# 513_lora_raspberrypi.net
KiCad netlist of a schematic drawn in EAGLE
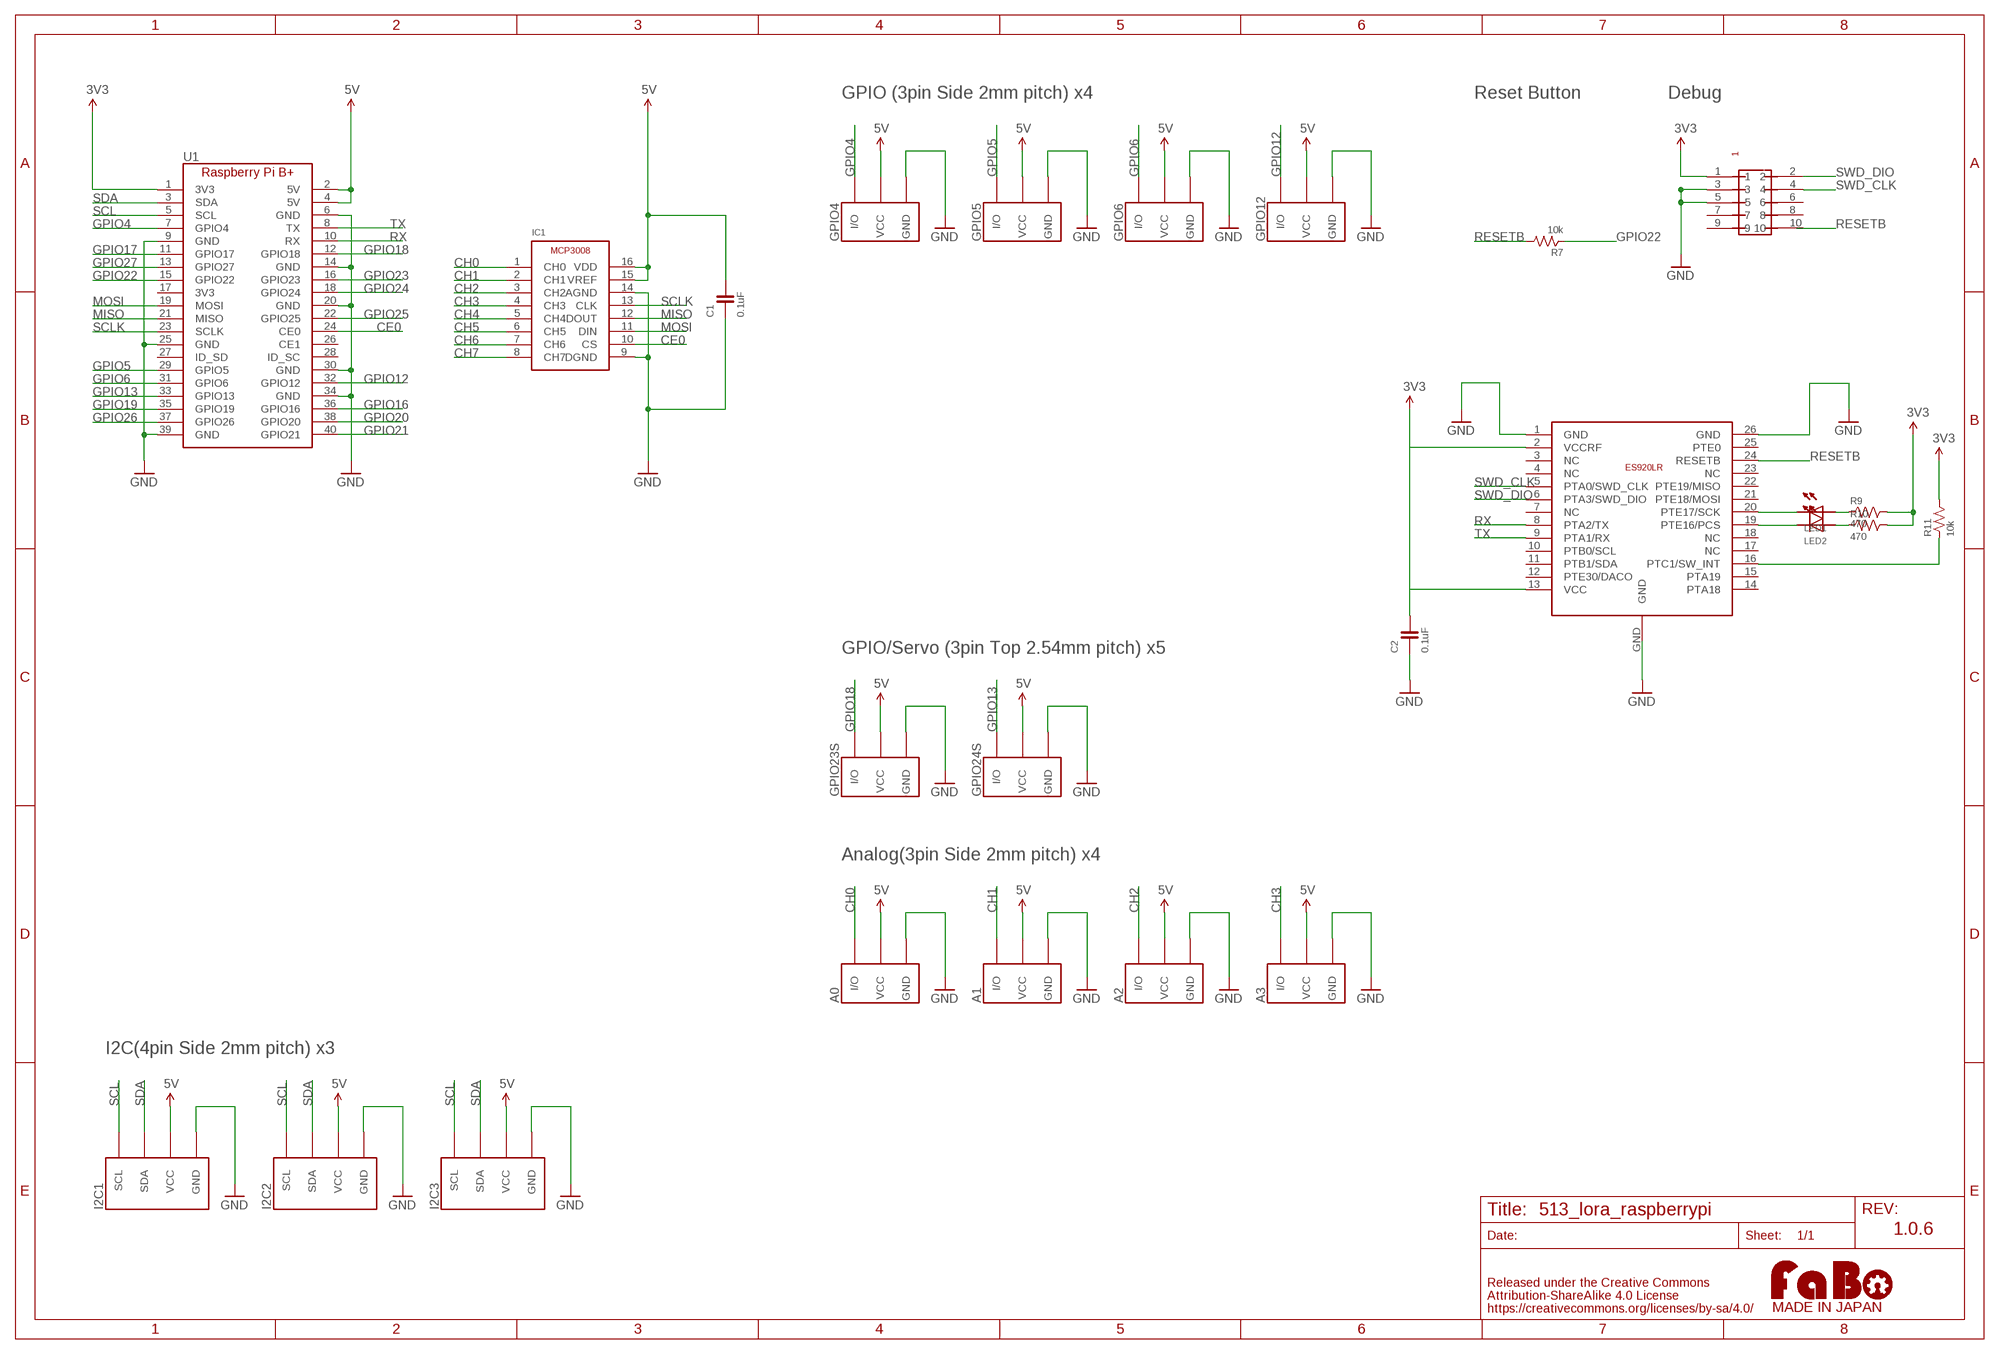
[diagram p0: schematic, sheet 1]

(export (version "E")
  (design (tool "Eeschema 10.0.6"))
  (components
    (comp (ref "A0")
      (value "FABO_BRICK_3PIN-B03B-PASK-1")
      (footprint "eagle-import:FABO_BRICK_3PIN_B03B-PASK-1")
      (libsource (lib "eagle-import") (part "FABO_BRICK_3PIN-B03B-PASK-1"))
    )
    (comp (ref "A1")
      (value "FABO_BRICK_3PIN-B03B-PASK-1")
      (footprint "eagle-import:FABO_BRICK_3PIN_B03B-PASK-1")
      (libsource (lib "eagle-import") (part "FABO_BRICK_3PIN-B03B-PASK-1"))
    )
    (comp (ref "A2")
      (value "FABO_BRICK_3PIN-B03B-PASK-1")
      (footprint "eagle-import:FABO_BRICK_3PIN_B03B-PASK-1")
      (libsource (lib "eagle-import") (part "FABO_BRICK_3PIN-B03B-PASK-1"))
    )
    (comp (ref "A3")
      (value "FABO_BRICK_3PIN-B03B-PASK-1")
      (footprint "eagle-import:FABO_BRICK_3PIN_B03B-PASK-1")
      (libsource (lib "eagle-import") (part "FABO_BRICK_3PIN-B03B-PASK-1"))
    )
    (comp (ref "C1")
      (value "0.1uF")
      (footprint "eagle-import:0603")
      (libsource (lib "eagle-import") (part "CAPACITOR-0603"))
    )
    (comp (ref "C2")
      (value "0.1uF")
      (footprint "eagle-import:0603-NARROW")
      (libsource (lib "eagle-import") (part "CAPACITOR-0603_NARROW"))
    )
    (comp (ref "GPIO4")
      (value "FABO_BRICK_3PIN-S03B-PASK-2")
      (footprint "eagle-import:FABO_BRICK_3PIN_S03B-PASK-2")
      (libsource (lib "eagle-import") (part "FABO_BRICK_3PIN-S03B-PASK-2"))
    )
    (comp (ref "GPIO5")
      (value "FABO_BRICK_3PIN-S03B-PASK-2")
      (footprint "eagle-import:FABO_BRICK_3PIN_S03B-PASK-2")
      (libsource (lib "eagle-import") (part "FABO_BRICK_3PIN-S03B-PASK-2"))
    )
    (comp (ref "GPIO6")
      (value "FABO_BRICK_3PIN-S03B-PASK-2")
      (footprint "eagle-import:FABO_BRICK_3PIN_S03B-PASK-2")
      (libsource (lib "eagle-import") (part "FABO_BRICK_3PIN-S03B-PASK-2"))
    )
    (comp (ref "GPIO12")
      (value "FABO_BRICK_3PIN-S03B-PASK-2")
      (footprint "eagle-import:FABO_BRICK_3PIN_S03B-PASK-2")
      (libsource (lib "eagle-import") (part "FABO_BRICK_3PIN-S03B-PASK-2"))
    )
    (comp (ref "GPIO23S")
      (value "FABO_BRICK_3PIN-HEADER")
      (footprint "eagle-import:FABO_BRICK_3PIN_HEADER")
      (libsource (lib "eagle-import") (part "FABO_BRICK_3PIN-HEADER"))
    )
    (comp (ref "GPIO24S")
      (value "FABO_BRICK_3PIN-HEADER")
      (footprint "eagle-import:FABO_BRICK_3PIN_HEADER")
      (libsource (lib "eagle-import") (part "FABO_BRICK_3PIN-HEADER"))
    )
    (comp (ref "I2C1")
      (value "FABO_BRICK_I2C-S04B-PASK-2")
      (footprint "eagle-import:FABO_BRICK_I2C_S04B-PASK-2")
      (libsource (lib "eagle-import") (part "FABO_BRICK_I2C-S04B-PASK-2"))
    )
    (comp (ref "I2C2")
      (value "FABO_BRICK_I2C-S04B-PASK-2")
      (footprint "eagle-import:FABO_BRICK_I2C_S04B-PASK-2")
      (libsource (lib "eagle-import") (part "FABO_BRICK_I2C-S04B-PASK-2"))
    )
    (comp (ref "I2C3")
      (value "FABO_BRICK_I2C-S04B-PASK-2")
      (footprint "eagle-import:FABO_BRICK_I2C_S04B-PASK-2")
      (libsource (lib "eagle-import") (part "FABO_BRICK_I2C-S04B-PASK-2"))
    )
    (comp (ref "IC1")
      (value "MICROCHIP-MCP3008")
      (footprint "eagle-import:MICROCHIP-MCP3008")
      (libsource (lib "eagle-import") (part "MICROCHIP-MCP3008"))
    )
    (comp (ref "LED1")
      (value "LED-0603")
      (footprint "eagle-import:0603")
      (libsource (lib "eagle-import") (part "LED-0603"))
    )
    (comp (ref "LED2")
      (value "LED-0603")
      (footprint "eagle-import:0603")
      (libsource (lib "eagle-import") (part "LED-0603"))
    )
    (comp (ref "R7")
      (value "10k")
      (footprint "eagle-import:0603-NARROW")
      (libsource (lib "eagle-import") (part "RESISTOR-0603-NARROW"))
    )
    (comp (ref "R9")
      (value "470")
      (footprint "eagle-import:0603-NARROW")
      (libsource (lib "eagle-import") (part "RESISTOR-0603-NARROW"))
    )
    (comp (ref "R10")
      (value "470")
      (footprint "eagle-import:0603-NARROW")
      (libsource (lib "eagle-import") (part "RESISTOR-0603-NARROW"))
    )
    (comp (ref "R11")
      (value "10k")
      (footprint "eagle-import:0603-NARROW")
      (libsource (lib "eagle-import") (part "RESISTOR-0603-NARROW"))
    )
    (comp (ref "U$14")
      (value "LOGO_FABO-M")
      (footprint "eagle-import:LOGO_FABO_MS")
      (libsource (lib "eagle-import") (part "LOGO_FABO-M"))
    )
    (comp (ref "U$15")
      (value "PIN-HEADER-SMT(1.27MM)2X5")
      (footprint "eagle-import:PIN-HEADER-SMT(1.27MM)2X5")
      (libsource (lib "eagle-import") (part "PIN-HEADER-SMT(1.27MM)2X5"))
    )
    (comp (ref "U$16")
      (value "ES920LR")
      (footprint "eagle-import:ES920LR")
      (libsource (lib "eagle-import") (part "ES920LR"))
    )
    (comp (ref "U1")
      (value "RASPBERRY_PI_B+")
      (footprint "eagle-import:RASPBERRY_PI_B+")
      (libsource (lib "eagle-import") (part "RASPBERRY_PI_B+"))
    )
  )
  (nets
    (net (code "1") (name "/CE0") (class "Default")
      (node (ref "IC1") (pin "10") (pinfunction "CS_10") (pintype "bidirectional"))
      (node (ref "U1") (pin "24") (pinfunction "CE0_24") (pintype "bidirectional"))
    )
    (net (code "2") (name "/CH0") (class "Default")
      (node (ref "A0") (pin "I/O") (pinfunction "I/O_I/O") (pintype "bidirectional"))
      (node (ref "IC1") (pin "1") (pinfunction "CH0_1") (pintype "bidirectional"))
    )
    (net (code "3") (name "/CH1") (class "Default")
      (node (ref "A1") (pin "I/O") (pinfunction "I/O_I/O") (pintype "bidirectional"))
      (node (ref "IC1") (pin "2") (pinfunction "CH1_2") (pintype "bidirectional"))
    )
    (net (code "4") (name "/CH2") (class "Default")
      (node (ref "A2") (pin "I/O") (pinfunction "I/O_I/O") (pintype "bidirectional"))
      (node (ref "IC1") (pin "3") (pinfunction "CH2_3") (pintype "bidirectional"))
    )
    (net (code "5") (name "/CH3") (class "Default")
      (node (ref "A3") (pin "I/O") (pinfunction "I/O_I/O") (pintype "bidirectional"))
      (node (ref "IC1") (pin "4") (pinfunction "CH3_4") (pintype "bidirectional"))
    )
    (net (code "6") (name "/CH4") (class "Default")
      (node (ref "IC1") (pin "5") (pinfunction "CH4_5") (pintype "bidirectional"))
    )
    (net (code "7") (name "/CH5") (class "Default")
      (node (ref "IC1") (pin "6") (pinfunction "CH5_6") (pintype "bidirectional"))
    )
    (net (code "8") (name "/CH6") (class "Default")
      (node (ref "IC1") (pin "7") (pinfunction "CH6_7") (pintype "bidirectional"))
    )
    (net (code "9") (name "/CH7") (class "Default")
      (node (ref "IC1") (pin "8") (pinfunction "CH7_8") (pintype "bidirectional"))
    )
    (net (code "10") (name "/GPIO4") (class "Default")
      (node (ref "GPIO4") (pin "I/O") (pinfunction "I/O_I/O") (pintype "bidirectional"))
      (node (ref "U1") (pin "7") (pinfunction "GPIO4_7") (pintype "bidirectional"))
    )
    (net (code "11") (name "/GPIO5") (class "Default")
      (node (ref "GPIO5") (pin "I/O") (pinfunction "I/O_I/O") (pintype "bidirectional"))
      (node (ref "U1") (pin "29") (pinfunction "GPIO5_29") (pintype "bidirectional"))
    )
    (net (code "12") (name "/GPIO6") (class "Default")
      (node (ref "GPIO6") (pin "I/O") (pinfunction "I/O_I/O") (pintype "bidirectional"))
      (node (ref "U1") (pin "31") (pinfunction "GPIO6_31") (pintype "bidirectional"))
    )
    (net (code "13") (name "/GPIO12") (class "Default")
      (node (ref "GPIO12") (pin "I/O") (pinfunction "I/O_I/O") (pintype "bidirectional"))
      (node (ref "U1") (pin "32") (pinfunction "GPIO12_32") (pintype "bidirectional"))
    )
    (net (code "14") (name "/GPIO13") (class "Default")
      (node (ref "GPIO24S") (pin "I/O") (pinfunction "I/O_I/O") (pintype "bidirectional"))
      (node (ref "U1") (pin "33") (pinfunction "GPIO13_33") (pintype "bidirectional"))
    )
    (net (code "15") (name "/GPIO16") (class "Default")
      (node (ref "U1") (pin "36") (pinfunction "GPIO16_36") (pintype "bidirectional"))
    )
    (net (code "16") (name "/GPIO17") (class "Default")
      (node (ref "U1") (pin "11") (pinfunction "GPIO17_11") (pintype "bidirectional"))
    )
    (net (code "17") (name "/GPIO18") (class "Default")
      (node (ref "GPIO23S") (pin "I/O") (pinfunction "I/O_I/O") (pintype "bidirectional"))
      (node (ref "U1") (pin "12") (pinfunction "GPIO18_12") (pintype "bidirectional"))
    )
    (net (code "18") (name "/GPIO19") (class "Default")
      (node (ref "U1") (pin "35") (pinfunction "GPIO19_35") (pintype "bidirectional"))
    )
    (net (code "19") (name "/GPIO20") (class "Default")
      (node (ref "U1") (pin "38") (pinfunction "GPIO20_38") (pintype "bidirectional"))
    )
    (net (code "20") (name "/GPIO21") (class "Default")
      (node (ref "U1") (pin "40") (pinfunction "GPIO21_40") (pintype "bidirectional"))
    )
    (net (code "21") (name "/GPIO22") (class "Default")
      (node (ref "R7") (pin "1") (pinfunction "1_1") (pintype "bidirectional"))
      (node (ref "U1") (pin "15") (pinfunction "GPIO22_15") (pintype "bidirectional"))
    )
    (net (code "22") (name "/GPIO23") (class "Default")
      (node (ref "U1") (pin "16") (pinfunction "GPIO23_16") (pintype "bidirectional"))
    )
    (net (code "23") (name "/GPIO24") (class "Default")
      (node (ref "U1") (pin "18") (pinfunction "GPIO24_18") (pintype "bidirectional"))
    )
    (net (code "24") (name "/GPIO25") (class "Default")
      (node (ref "U1") (pin "22") (pinfunction "GPIO25_22") (pintype "bidirectional"))
    )
    (net (code "25") (name "/GPIO26") (class "Default")
      (node (ref "U1") (pin "37") (pinfunction "GPIO26_37") (pintype "bidirectional"))
    )
    (net (code "26") (name "/GPIO27") (class "Default")
      (node (ref "U1") (pin "13") (pinfunction "GPIO27_13") (pintype "bidirectional"))
    )
    (net (code "27") (name "/MISO") (class "Default")
      (node (ref "IC1") (pin "12") (pinfunction "DOUT_12") (pintype "bidirectional"))
      (node (ref "U1") (pin "21") (pinfunction "MISO_21") (pintype "bidirectional"))
    )
    (net (code "28") (name "/MOSI") (class "Default")
      (node (ref "IC1") (pin "11") (pinfunction "DIN_11") (pintype "bidirectional"))
      (node (ref "U1") (pin "19") (pinfunction "MOSI_19") (pintype "bidirectional"))
    )
    (net (code "29") (name "/RESETB") (class "Default")
      (node (ref "R7") (pin "2") (pinfunction "2_2") (pintype "bidirectional"))
      (node (ref "U$15") (pin "10") (pinfunction "10_10") (pintype "bidirectional"))
      (node (ref "U$16") (pin "24") (pinfunction "RESETB_24") (pintype "bidirectional"))
    )
    (net (code "30") (name "/RX") (class "Default")
      (node (ref "U$16") (pin "8") (pinfunction "PTA2/TX_8") (pintype "bidirectional"))
      (node (ref "U1") (pin "10") (pinfunction "RX_10") (pintype "bidirectional"))
    )
    (net (code "31") (name "/SCL") (class "Default")
      (node (ref "I2C1") (pin "SCL") (pinfunction "SCL_SCL") (pintype "bidirectional"))
      (node (ref "I2C2") (pin "SCL") (pinfunction "SCL_SCL") (pintype "bidirectional"))
      (node (ref "I2C3") (pin "SCL") (pinfunction "SCL_SCL") (pintype "bidirectional"))
      (node (ref "U1") (pin "5") (pinfunction "SCL_5") (pintype "bidirectional"))
    )
    (net (code "32") (name "/SCLK") (class "Default")
      (node (ref "IC1") (pin "13") (pinfunction "CLK_13") (pintype "bidirectional"))
      (node (ref "U1") (pin "23") (pinfunction "SCLK_23") (pintype "bidirectional"))
    )
    (net (code "33") (name "/SDA") (class "Default")
      (node (ref "I2C1") (pin "SDA") (pinfunction "SDA_SDA") (pintype "bidirectional"))
      (node (ref "I2C2") (pin "SDA") (pinfunction "SDA_SDA") (pintype "bidirectional"))
      (node (ref "I2C3") (pin "SDA") (pinfunction "SDA_SDA") (pintype "bidirectional"))
      (node (ref "U1") (pin "3") (pinfunction "SDA_3") (pintype "bidirectional"))
    )
    (net (code "34") (name "/SWD_CLK") (class "Default")
      (node (ref "U$15") (pin "4") (pinfunction "4_4") (pintype "bidirectional"))
      (node (ref "U$16") (pin "5") (pinfunction "PTA0/SWD_CLK_5") (pintype "bidirectional"))
    )
    (net (code "35") (name "/SWD_DIO") (class "Default")
      (node (ref "U$15") (pin "2") (pinfunction "2_2") (pintype "bidirectional"))
      (node (ref "U$16") (pin "6") (pinfunction "PTA3/SWD_DIO_6") (pintype "bidirectional"))
    )
    (net (code "36") (name "/TX") (class "Default")
      (node (ref "U$16") (pin "9") (pinfunction "PTA1/RX_9") (pintype "bidirectional"))
      (node (ref "U1") (pin "8") (pinfunction "TX_8") (pintype "bidirectional"))
    )
    (net (code "37") (name "3V3") (class "Default")
      (node (ref "C2") (pin "2") (pinfunction "2_2") (pintype "passive"))
      (node (ref "R10") (pin "2") (pinfunction "2_2") (pintype "bidirectional"))
      (node (ref "R11") (pin "2") (pinfunction "2_2") (pintype "bidirectional"))
      (node (ref "R9") (pin "2") (pinfunction "2_2") (pintype "bidirectional"))
      (node (ref "U$15") (pin "1") (pinfunction "1_1") (pintype "bidirectional"))
      (node (ref "U$16") (pin "13") (pinfunction "VCC_13") (pintype "bidirectional"))
      (node (ref "U$16") (pin "2") (pinfunction "VCCRF_2") (pintype "bidirectional"))
      (node (ref "U1") (pin "1") (pinfunction "3V3_1") (pintype "bidirectional"))
    )
    (net (code "38") (name "5V") (class "Default")
      (node (ref "A0") (pin "VCC") (pinfunction "VCC_VCC") (pintype "bidirectional"))
      (node (ref "A1") (pin "VCC") (pinfunction "VCC_VCC") (pintype "bidirectional"))
      (node (ref "A2") (pin "VCC") (pinfunction "VCC_VCC") (pintype "bidirectional"))
      (node (ref "A3") (pin "VCC") (pinfunction "VCC_VCC") (pintype "bidirectional"))
      (node (ref "C1") (pin "2") (pinfunction "2_2") (pintype "passive"))
      (node (ref "GPIO12") (pin "VCC") (pinfunction "VCC_VCC") (pintype "bidirectional"))
      (node (ref "GPIO23S") (pin "VCC") (pinfunction "VCC_VCC") (pintype "bidirectional"))
      (node (ref "GPIO24S") (pin "VCC") (pinfunction "VCC_VCC") (pintype "bidirectional"))
      (node (ref "GPIO4") (pin "VCC") (pinfunction "VCC_VCC") (pintype "bidirectional"))
      (node (ref "GPIO5") (pin "VCC") (pinfunction "VCC_VCC") (pintype "bidirectional"))
      (node (ref "GPIO6") (pin "VCC") (pinfunction "VCC_VCC") (pintype "bidirectional"))
      (node (ref "I2C1") (pin "VCC") (pinfunction "VCC_VCC") (pintype "bidirectional"))
      (node (ref "I2C2") (pin "VCC") (pinfunction "VCC_VCC") (pintype "bidirectional"))
      (node (ref "I2C3") (pin "VCC") (pinfunction "VCC_VCC") (pintype "bidirectional"))
      (node (ref "IC1") (pin "15") (pinfunction "VREF_15") (pintype "bidirectional"))
      (node (ref "IC1") (pin "16") (pinfunction "VDD_16") (pintype "bidirectional"))
      (node (ref "U1") (pin "2") (pinfunction "5V_2") (pintype "bidirectional"))
      (node (ref "U1") (pin "4") (pinfunction "5V_4") (pintype "bidirectional"))
    )
    (net (code "39") (name "GND") (class "Default")
      (node (ref "A0") (pin "GND") (pinfunction "GND_GND") (pintype "bidirectional"))
      (node (ref "A1") (pin "GND") (pinfunction "GND_GND") (pintype "bidirectional"))
      (node (ref "A2") (pin "GND") (pinfunction "GND_GND") (pintype "bidirectional"))
      (node (ref "A3") (pin "GND") (pinfunction "GND_GND") (pintype "bidirectional"))
      (node (ref "C1") (pin "1") (pinfunction "1_1") (pintype "passive"))
      (node (ref "C2") (pin "1") (pinfunction "1_1") (pintype "passive"))
      (node (ref "GPIO12") (pin "GND") (pinfunction "GND_GND") (pintype "bidirectional"))
      (node (ref "GPIO23S") (pin "GND") (pinfunction "GND_GND") (pintype "bidirectional"))
      (node (ref "GPIO24S") (pin "GND") (pinfunction "GND_GND") (pintype "bidirectional"))
      (node (ref "GPIO4") (pin "GND") (pinfunction "GND_GND") (pintype "bidirectional"))
      (node (ref "GPIO5") (pin "GND") (pinfunction "GND_GND") (pintype "bidirectional"))
      (node (ref "GPIO6") (pin "GND") (pinfunction "GND_GND") (pintype "bidirectional"))
      (node (ref "I2C1") (pin "GND") (pinfunction "GND_GND") (pintype "bidirectional"))
      (node (ref "I2C2") (pin "GND") (pinfunction "GND_GND") (pintype "bidirectional"))
      (node (ref "I2C3") (pin "GND") (pinfunction "GND_GND") (pintype "bidirectional"))
      (node (ref "IC1") (pin "14") (pinfunction "AGND_14") (pintype "bidirectional"))
      (node (ref "IC1") (pin "9") (pinfunction "DGND_9") (pintype "bidirectional"))
      (node (ref "U$15") (pin "3") (pinfunction "3_3") (pintype "bidirectional"))
      (node (ref "U$15") (pin "5") (pinfunction "5_5") (pintype "bidirectional"))
      (node (ref "U$16") (pin "1") (pinfunction "GND_1") (pintype "bidirectional"))
      (node (ref "U$16") (pin "26") (pinfunction "GND_26") (pintype "bidirectional"))
      (node (ref "U$16") (pin "GND") (pinfunction "GND_GND") (pintype "bidirectional"))
      (node (ref "U1") (pin "14") (pinfunction "GND_14") (pintype "bidirectional"))
      (node (ref "U1") (pin "20") (pinfunction "GND_20") (pintype "bidirectional"))
      (node (ref "U1") (pin "25") (pinfunction "GND_25") (pintype "bidirectional"))
      (node (ref "U1") (pin "30") (pinfunction "GND_30") (pintype "bidirectional"))
      (node (ref "U1") (pin "34") (pinfunction "GND_34") (pintype "bidirectional"))
      (node (ref "U1") (pin "39") (pinfunction "GND_39") (pintype "bidirectional"))
      (node (ref "U1") (pin "6") (pinfunction "GND_6") (pintype "bidirectional"))
      (node (ref "U1") (pin "9") (pinfunction "GND_9") (pintype "bidirectional"))
    )
    (net (code "40") (name "Net-(LED1-PadANODE)") (class "Default")
      (node (ref "LED1") (pin "ANODE") (pinfunction "ANODE_ANODE") (pintype "passive"))
      (node (ref "R9") (pin "1") (pinfunction "1_1") (pintype "bidirectional"))
    )
    (net (code "41") (name "Net-(LED2-PadANODE)") (class "Default")
      (node (ref "LED2") (pin "ANODE") (pinfunction "ANODE_ANODE") (pintype "passive"))
      (node (ref "R10") (pin "1") (pinfunction "1_1") (pintype "bidirectional"))
    )
    (net (code "42") (name "Net-(U$16-PTC1{slash}SW_INT)") (class "Default")
      (node (ref "R11") (pin "1") (pinfunction "1_1") (pintype "bidirectional"))
      (node (ref "U$16") (pin "16") (pinfunction "PTC1/SW_INT_16") (pintype "bidirectional"))
    )
    (net (code "43") (name "Net-(U$16-PTE16{slash}PCS)") (class "Default")
      (node (ref "LED2") (pin "CATHODE") (pinfunction "CATHODE_CATHODE") (pintype "passive"))
      (node (ref "U$16") (pin "19") (pinfunction "PTE16/PCS_19") (pintype "bidirectional"))
    )
    (net (code "44") (name "Net-(U$16-PTE17{slash}SCK)") (class "Default")
      (node (ref "LED1") (pin "CATHODE") (pinfunction "CATHODE_CATHODE") (pintype "passive"))
      (node (ref "U$16") (pin "20") (pinfunction "PTE17/SCK_20") (pintype "bidirectional"))
    )
    (net (code "45") (name "unconnected-(U$15-Pad6)") (class "Default")
      (node (ref "U$15") (pin "6") (pinfunction "6_6") (pintype "bidirectional"))
    )
    (net (code "46") (name "unconnected-(U$15-Pad7)") (class "Default")
      (node (ref "U$15") (pin "7") (pinfunction "7_7") (pintype "bidirectional"))
    )
    (net (code "47") (name "unconnected-(U$15-Pad8)") (class "Default")
      (node (ref "U$15") (pin "8") (pinfunction "8_8") (pintype "bidirectional"))
    )
    (net (code "48") (name "unconnected-(U$15-Pad9)") (class "Default")
      (node (ref "U$15") (pin "9") (pinfunction "9_9") (pintype "bidirectional"))
    )
    (net (code "49") (name "unconnected-(U$16-NC-Pad3)") (class "Default")
      (node (ref "U$16") (pin "3") (pinfunction "NC_3") (pintype "bidirectional"))
    )
    (net (code "50") (name "unconnected-(U$16-NC-Pad4)") (class "Default")
      (node (ref "U$16") (pin "4") (pinfunction "NC_4") (pintype "bidirectional"))
    )
    (net (code "51") (name "unconnected-(U$16-NC-Pad7)") (class "Default")
      (node (ref "U$16") (pin "7") (pinfunction "NC_7") (pintype "bidirectional"))
    )
    (net (code "52") (name "unconnected-(U$16-NC-Pad17)") (class "Default")
      (node (ref "U$16") (pin "17") (pinfunction "NC_17") (pintype "bidirectional"))
    )
    (net (code "53") (name "unconnected-(U$16-NC-Pad18)") (class "Default")
      (node (ref "U$16") (pin "18") (pinfunction "NC_18") (pintype "bidirectional"))
    )
    (net (code "54") (name "unconnected-(U$16-NC-Pad23)") (class "Default")
      (node (ref "U$16") (pin "23") (pinfunction "NC_23") (pintype "bidirectional"))
    )
    (net (code "55") (name "unconnected-(U$16-PTA18-Pad14)") (class "Default")
      (node (ref "U$16") (pin "14") (pinfunction "PTA18_14") (pintype "bidirectional"))
    )
    (net (code "56") (name "unconnected-(U$16-PTA19-Pad15)") (class "Default")
      (node (ref "U$16") (pin "15") (pinfunction "PTA19_15") (pintype "bidirectional"))
    )
    (net (code "57") (name "unconnected-(U$16-PTB0{slash}SCL-Pad10)") (class "Default")
      (node (ref "U$16") (pin "10") (pinfunction "PTB0/SCL_10") (pintype "bidirectional"))
    )
    (net (code "58") (name "unconnected-(U$16-PTB1{slash}SDA-Pad11)") (class "Default")
      (node (ref "U$16") (pin "11") (pinfunction "PTB1/SDA_11") (pintype "bidirectional"))
    )
    (net (code "59") (name "unconnected-(U$16-PTE0-Pad25)") (class "Default")
      (node (ref "U$16") (pin "25") (pinfunction "PTE0_25") (pintype "bidirectional"))
    )
    (net (code "60") (name "unconnected-(U$16-PTE18{slash}MOSI-Pad21)") (class "Default")
      (node (ref "U$16") (pin "21") (pinfunction "PTE18/MOSI_21") (pintype "bidirectional"))
    )
    (net (code "61") (name "unconnected-(U$16-PTE19{slash}MISO-Pad22)") (class "Default")
      (node (ref "U$16") (pin "22") (pinfunction "PTE19/MISO_22") (pintype "bidirectional"))
    )
    (net (code "62") (name "unconnected-(U$16-PTE30{slash}DACO-Pad12)") (class "Default")
      (node (ref "U$16") (pin "12") (pinfunction "PTE30/DACO_12") (pintype "bidirectional"))
    )
    (net (code "63") (name "unconnected-(U1-3V3-Pad17)") (class "Default")
      (node (ref "U1") (pin "17") (pinfunction "3V3_17") (pintype "bidirectional"))
    )
    (net (code "64") (name "unconnected-(U1-CE1-Pad26)") (class "Default")
      (node (ref "U1") (pin "26") (pinfunction "CE1_26") (pintype "bidirectional"))
    )
    (net (code "65") (name "unconnected-(U1-ID_SC-Pad28)") (class "Default")
      (node (ref "U1") (pin "28") (pinfunction "ID_SC_28") (pintype "bidirectional"))
    )
    (net (code "66") (name "unconnected-(U1-ID_SD-Pad27)") (class "Default")
      (node (ref "U1") (pin "27") (pinfunction "ID_SD_27") (pintype "bidirectional"))
    )
  )
)
